# DEBUG.net
KiCad netlist of a schematic drawn in Altium Designer
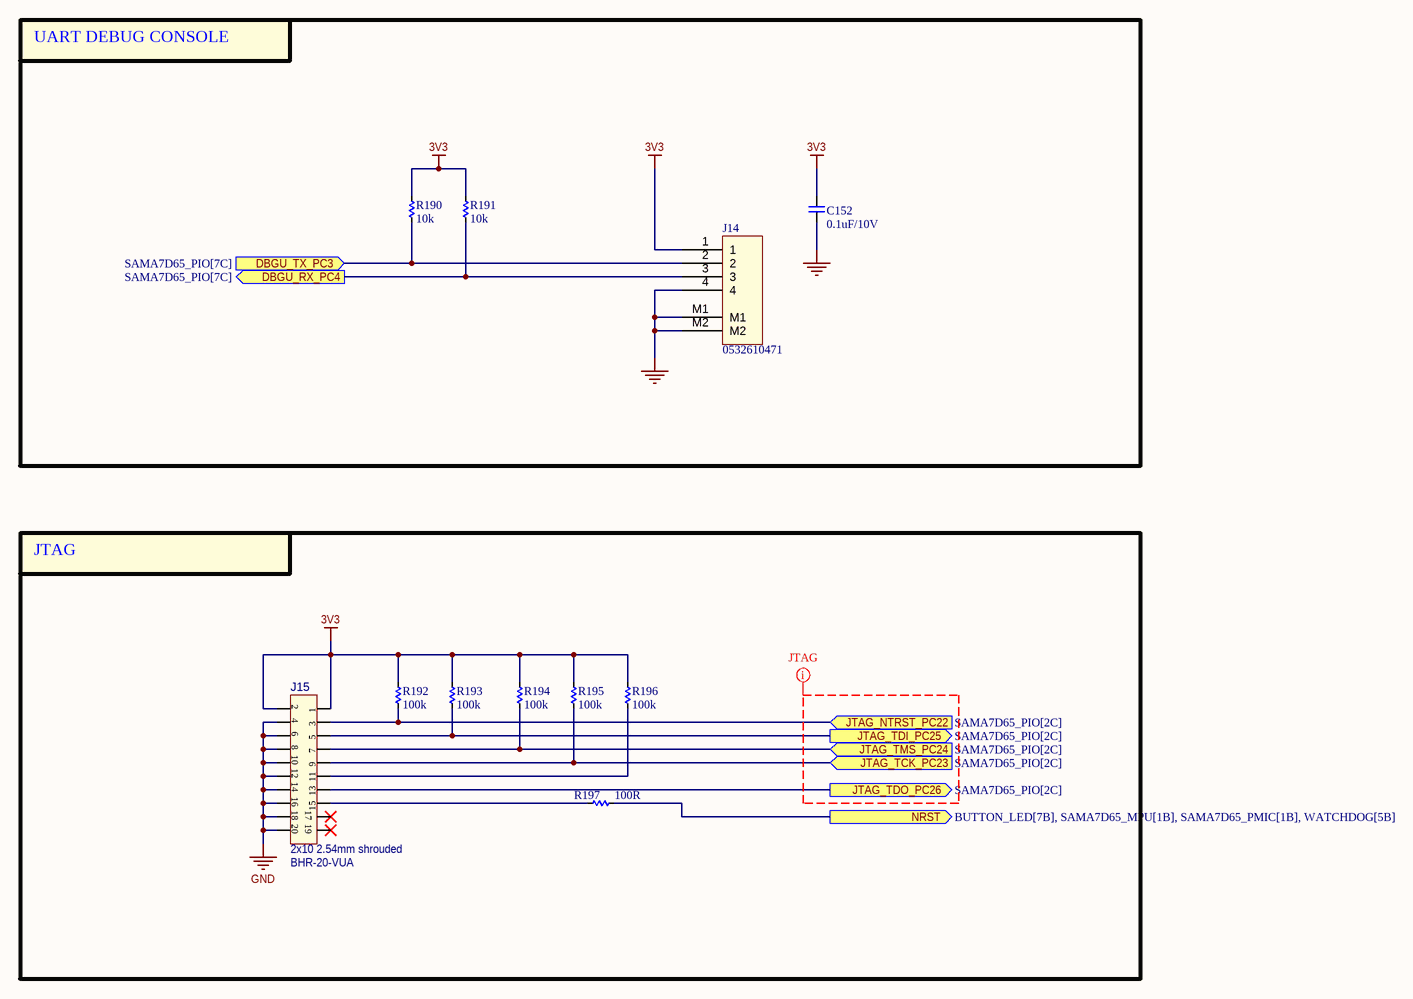
[diagram p0: DEBUG.SchDoc]

(export (version "E")
  (design (tool "Eeschema 10.0.6"))
  (components
    (comp (ref "C152")
      (value "0.1uF/10V")
      (footprint "CAP_C_1005X50_L")
      (description "CAP CHIP")
      (libsource (lib "IFBschelib") (part "_CAP_C_2"))
    )
    (comp (ref "J14")
      (value "0532610471")
      (footprint "MOLEX_0532610471")
      (libsource (lib "IFBschelib") (part "Header 4x1_2M"))
    )
    (comp (ref "J15")
      (value "2x10 2.54mm shrouded")
      (footprint "HDR_M_2.54_2X10_SBH11-PBPC-D10-ST-BK")
      (fields
        (field (name "VOLTAGE") "250VAC")
        (field (name "MANUFACTURER PART NUMBER 1") "BHR-20-VUA")
        (field (name "Comment") "Header 2x10")
        (field (name "OWNER") "Dragos Danaila")
      )
      (libsource (lib "IFBschelib") (part "CON2625"))
    )
    (comp (ref "R190")
      (value "10k")
      (footprint "RES_C_1005x30_L")
      (description "RES")
      (libsource (lib "IFBschelib") (part "_RES_B_2"))
    )
    (comp (ref "R191")
      (value "10k")
      (footprint "RES_C_1005x30_L")
      (description "RES")
      (libsource (lib "IFBschelib") (part "_RES_B_2"))
    )
    (comp (ref "R192")
      (value "100k")
      (footprint "RES_C_1005x30_L")
      (description "RES")
      (libsource (lib "IFBschelib") (part "_RES_B_2"))
    )
    (comp (ref "R193")
      (value "100k")
      (footprint "RES_C_1005x30_L")
      (description "RES")
      (libsource (lib "IFBschelib") (part "_RES_B_2"))
    )
    (comp (ref "R194")
      (value "100k")
      (footprint "RES_C_1005x30_L")
      (description "RES")
      (libsource (lib "IFBschelib") (part "_RES_B_2"))
    )
    (comp (ref "R195")
      (value "100k")
      (footprint "RES_C_1005x30_L")
      (description "RES")
      (libsource (lib "IFBschelib") (part "_RES_B_2"))
    )
    (comp (ref "R196")
      (value "100k")
      (footprint "RES_C_1005x30_L")
      (description "RES")
      (libsource (lib "IFBschelib") (part "_RES_B_2"))
    )
    (comp (ref "R197")
      (value "100R")
      (footprint "RES_C_1005x30_L")
      (description "RES")
      (libsource (lib "IFBschelib") (part "_RES_B_2"))
    )
  )
  (nets
    (net (code "1") (name "/DBGU_RX_PC4") (class "Default")
      (node (ref "J14") (pin "3") (pinfunction "3_3") (pintype "passive"))
      (node (ref "R191") (pin "2") (pinfunction "2_2") (pintype "passive"))
    )
    (net (code "2") (name "/DBGU_TX_PC3") (class "Default")
      (node (ref "J14") (pin "2") (pinfunction "2_2") (pintype "passive"))
      (node (ref "R190") (pin "2") (pinfunction "2_2") (pintype "passive"))
    )
    (net (code "3") (name "/JTAG_NTRST_PC22") (class "Default")
      (node (ref "J15") (pin "3") (pinfunction "3_3") (pintype "passive"))
      (node (ref "R192") (pin "1") (pinfunction "1_1") (pintype "passive"))
    )
    (net (code "4") (name "/JTAG_TCK_PC23") (class "Default")
      (node (ref "J15") (pin "9") (pinfunction "9_9") (pintype "passive"))
      (node (ref "R195") (pin "1") (pinfunction "1_1") (pintype "passive"))
    )
    (net (code "5") (name "/JTAG_TDI_PC25") (class "Default")
      (node (ref "J15") (pin "5") (pinfunction "5_5") (pintype "passive"))
      (node (ref "R193") (pin "1") (pinfunction "1_1") (pintype "passive"))
    )
    (net (code "6") (name "/JTAG_TDO_PC26") (class "Default")
      (node (ref "J15") (pin "13") (pinfunction "13_13") (pintype "passive"))
    )
    (net (code "7") (name "/JTAG_TMS_PC24") (class "Default")
      (node (ref "J15") (pin "7") (pinfunction "7_7") (pintype "passive"))
      (node (ref "R194") (pin "1") (pinfunction "1_1") (pintype "passive"))
    )
    (net (code "8") (name "/NRST") (class "Default")
      (node (ref "R197") (pin "2") (pinfunction "2_2") (pintype "passive"))
    )
    (net (code "9") (name "3V3") (class "Default")
      (node (ref "C152") (pin "2") (pinfunction "2_2") (pintype "passive"))
      (node (ref "J14") (pin "1") (pinfunction "1_1") (pintype "passive"))
      (node (ref "J15") (pin "1") (pinfunction "1_1") (pintype "passive"))
      (node (ref "J15") (pin "2") (pinfunction "2_2") (pintype "passive"))
      (node (ref "R190") (pin "1") (pinfunction "1_1") (pintype "passive"))
      (node (ref "R191") (pin "1") (pinfunction "1_1") (pintype "passive"))
      (node (ref "R192") (pin "2") (pinfunction "2_2") (pintype "passive"))
      (node (ref "R193") (pin "2") (pinfunction "2_2") (pintype "passive"))
      (node (ref "R194") (pin "2") (pinfunction "2_2") (pintype "passive"))
      (node (ref "R195") (pin "2") (pinfunction "2_2") (pintype "passive"))
      (node (ref "R196") (pin "2") (pinfunction "2_2") (pintype "passive"))
    )
    (net (code "10") (name "GND") (class "Default")
      (node (ref "C152") (pin "1") (pinfunction "1_1") (pintype "passive"))
      (node (ref "J14") (pin "4") (pinfunction "4_4") (pintype "passive"))
      (node (ref "J14") (pin "M1") (pinfunction "M1_M1") (pintype "passive"))
      (node (ref "J14") (pin "M2") (pinfunction "M2_M2") (pintype "passive"))
      (node (ref "J15") (pin "10") (pinfunction "10_10") (pintype "passive"))
      (node (ref "J15") (pin "12") (pinfunction "12_12") (pintype "passive"))
      (node (ref "J15") (pin "14") (pinfunction "14_14") (pintype "passive"))
      (node (ref "J15") (pin "16") (pinfunction "16_16") (pintype "passive"))
      (node (ref "J15") (pin "18") (pinfunction "18_18") (pintype "passive"))
      (node (ref "J15") (pin "20") (pinfunction "20_20") (pintype "passive"))
      (node (ref "J15") (pin "4") (pinfunction "4_4") (pintype "passive"))
      (node (ref "J15") (pin "6") (pinfunction "6_6") (pintype "passive"))
      (node (ref "J15") (pin "8") (pinfunction "8_8") (pintype "passive"))
    )
    (net (code "11") (name "Net-(J15-Pad11)") (class "Default")
      (node (ref "J15") (pin "11") (pinfunction "11_11") (pintype "passive"))
      (node (ref "R196") (pin "1") (pinfunction "1_1") (pintype "passive"))
    )
    (net (code "12") (name "Net-(J15-Pad15)") (class "Default")
      (node (ref "J15") (pin "15") (pinfunction "15_15") (pintype "passive"))
      (node (ref "R197") (pin "1") (pinfunction "1_1") (pintype "passive"))
    )
    (net (code "13") (name "unconnected-(J15-Pad17)") (class "Default")
      (node (ref "J15") (pin "17") (pinfunction "17_17") (pintype "passive+no_connect"))
    )
    (net (code "14") (name "unconnected-(J15-Pad19)") (class "Default")
      (node (ref "J15") (pin "19") (pinfunction "19_19") (pintype "passive+no_connect"))
    )
  )
)
